# rp-schield.net
KiCad netlist of a schematic drawn in EAGLE
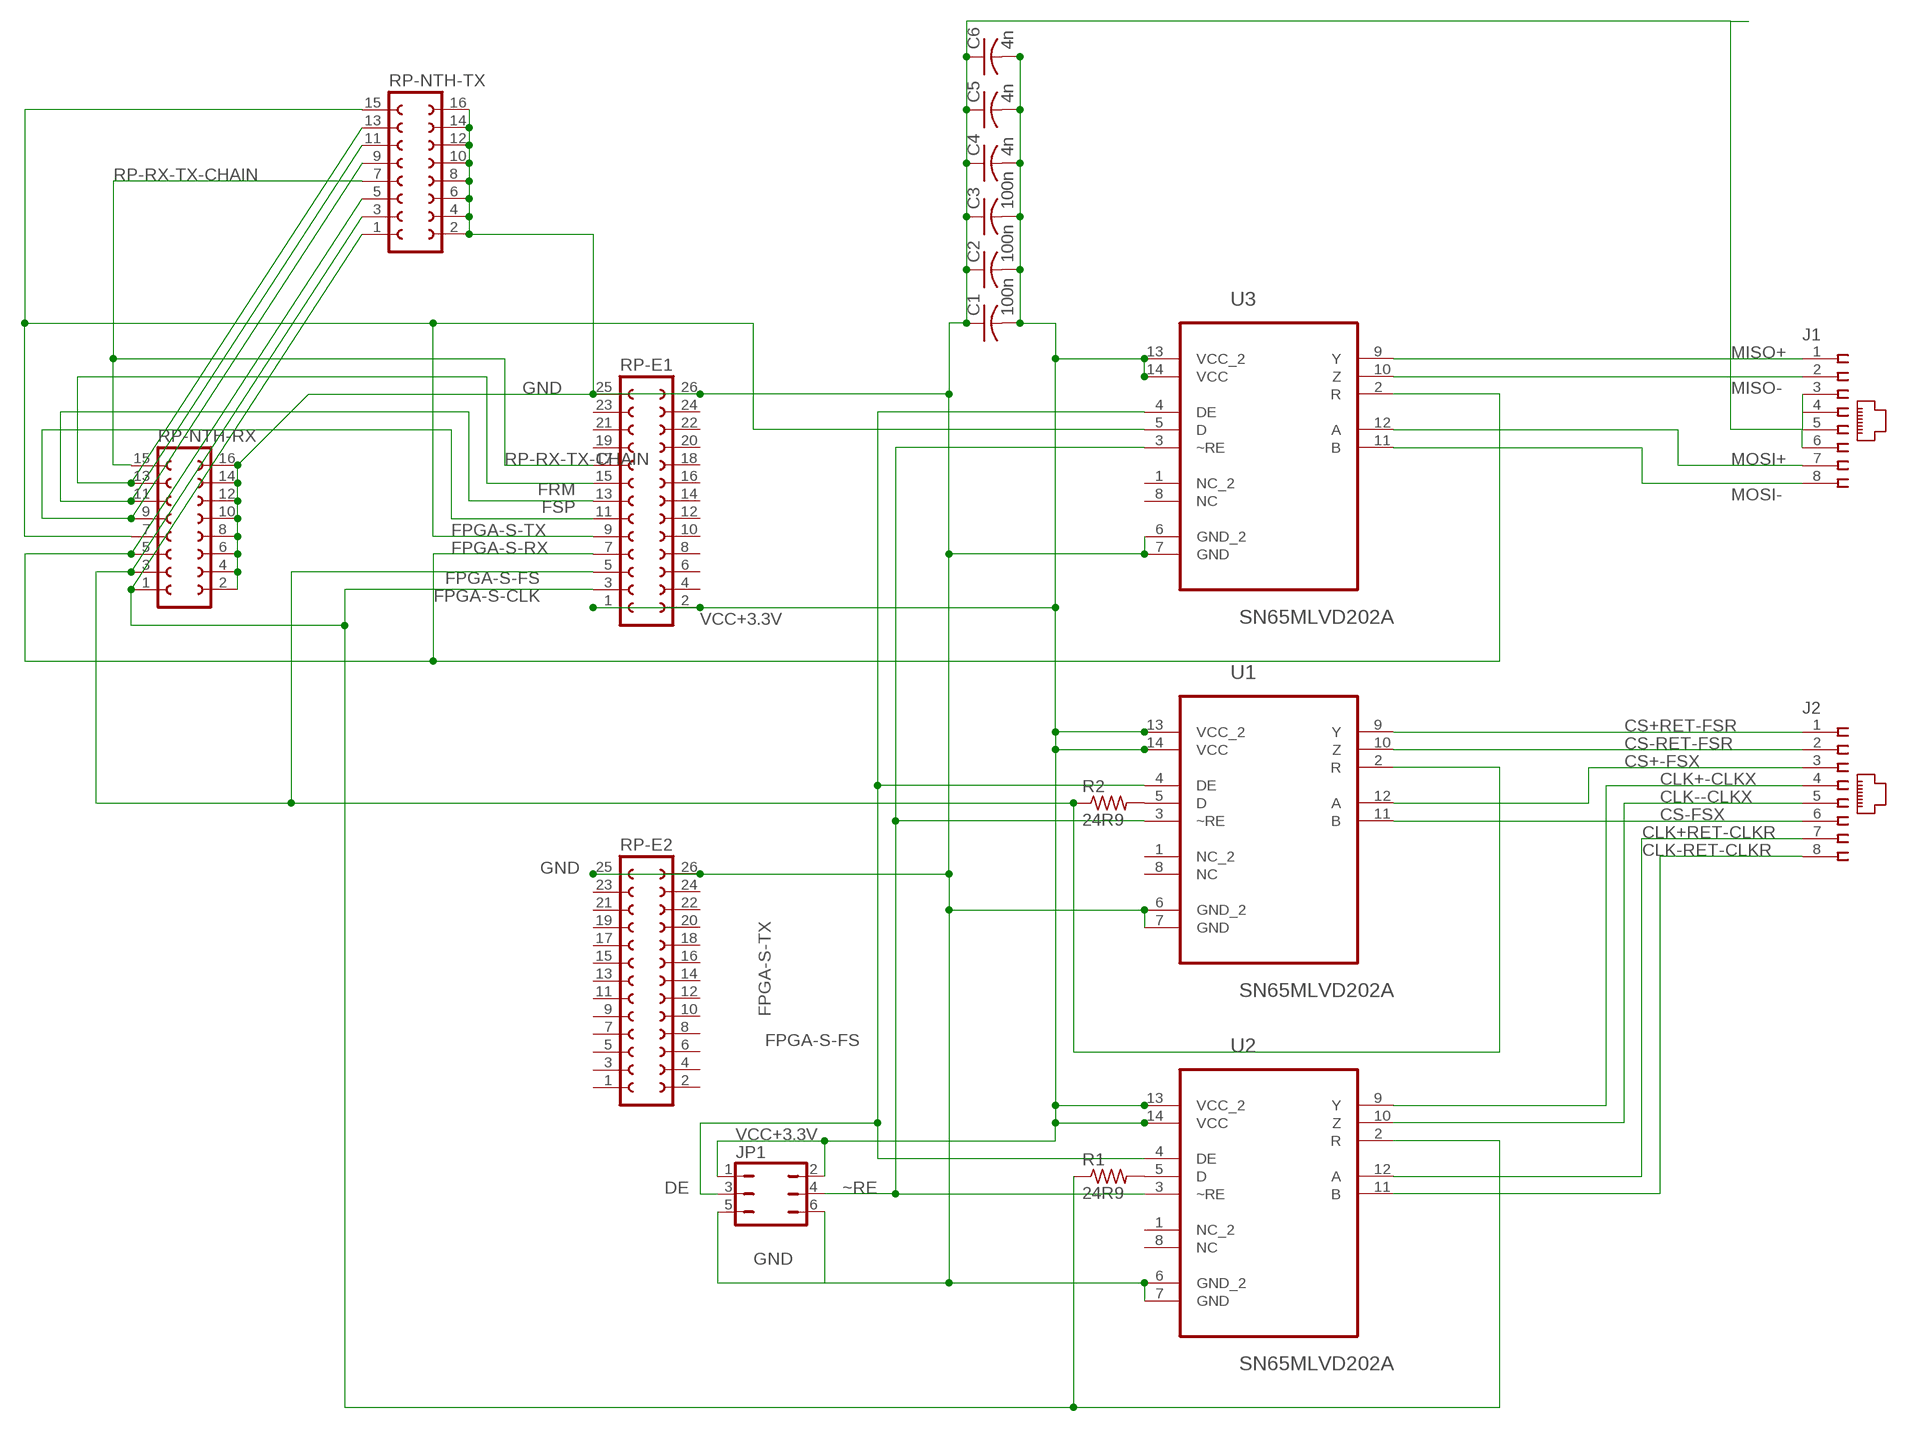
[diagram p0: schematic, sheet 1]

(export (version "E")
  (design (tool "Eeschema 10.0.6"))
  (components
    (comp (ref "C1")
      (value "100n")
      (footprint "eagle-import:C0805")
      (libsource (lib "eagle-import") (part "C-USC0805"))
    )
    (comp (ref "C2")
      (value "100n")
      (footprint "eagle-import:C0805")
      (libsource (lib "eagle-import") (part "C-USC0805"))
    )
    (comp (ref "C3")
      (value "100n")
      (footprint "eagle-import:C0805")
      (libsource (lib "eagle-import") (part "C-USC0805"))
    )
    (comp (ref "C4")
      (value "4n")
      (footprint "eagle-import:C0805")
      (libsource (lib "eagle-import") (part "C-USC0805"))
    )
    (comp (ref "C5")
      (value "4n")
      (footprint "eagle-import:C0805")
      (libsource (lib "eagle-import") (part "C-USC0805"))
    )
    (comp (ref "C6")
      (value "4n")
      (footprint "eagle-import:C0805")
      (libsource (lib "eagle-import") (part "C-USC0805"))
    )
    (comp (ref "J1")
      (value "557785-1-SHIELD")
      (footprint "eagle-import:557785-1")
      (libsource (lib "eagle-import") (part "557785-1-SHIELD"))
    )
    (comp (ref "J2")
      (value "557785-1-SHIELD")
      (footprint "eagle-import:557785-1")
      (libsource (lib "eagle-import") (part "557785-1-SHIELD"))
    )
    (comp (ref "JP1")
      (value "JP3Q")
      (footprint "eagle-import:JP3Q")
      (libsource (lib "eagle-import") (part "JP3Q"))
    )
    (comp (ref "R1")
      (value "24R9")
      (footprint "eagle-import:M1206")
      (libsource (lib "eagle-import") (part "R-US_M1206"))
    )
    (comp (ref "R2")
      (value "24R9")
      (footprint "eagle-import:M1206")
      (libsource (lib "eagle-import") (part "R-US_M1206"))
    )
    (comp (ref "RP-E1")
      (value "FE13-2")
      (footprint "eagle-import:FE13-2")
      (libsource (lib "eagle-import") (part "FE13-2"))
    )
    (comp (ref "RP-E2")
      (value "FE13-2")
      (footprint "eagle-import:FE13-2")
      (libsource (lib "eagle-import") (part "FE13-2"))
    )
    (comp (ref "RP-NTH-RX")
      (value "FE08-2")
      (footprint "eagle-import:FE08-2")
      (libsource (lib "eagle-import") (part "FE08-2"))
    )
    (comp (ref "RP-NTH-TX")
      (value "FE08-2")
      (footprint "eagle-import:FE08-2")
      (libsource (lib "eagle-import") (part "FE08-2"))
    )
    (comp (ref "U1")
      (value "SN65MLVD202A")
      (footprint "eagle-import:SOIC127P600X175-14N")
      (fields (field (name "MPN") "SN65MLVD205AD"))
      (libsource (lib "eagle-import") (part "SN65MLVD205AD"))
    )
    (comp (ref "U2")
      (value "SN65MLVD202A")
      (footprint "eagle-import:SOIC127P600X175-14N")
      (fields (field (name "MPN") "SN65MLVD205AD"))
      (libsource (lib "eagle-import") (part "SN65MLVD205AD"))
    )
    (comp (ref "U3")
      (value "SN65MLVD202A")
      (footprint "eagle-import:SOIC127P600X175-14N")
      (fields (field (name "MPN") "SN65MLVD205AD"))
      (libsource (lib "eagle-import") (part "SN65MLVD205AD"))
    )
  )
  (nets
    (net (code "1") (name "/CLK+-CLKX") (class "Default")
      (node (ref "J2") (pin "4") (pinfunction "4_4") (pintype "passive"))
      (node (ref "U2") (pin "9") (pinfunction "Y_9") (pintype "output"))
    )
    (net (code "2") (name "/CLK+RET-CLKR") (class "Default")
      (node (ref "J2") (pin "7") (pinfunction "7_7") (pintype "passive"))
      (node (ref "U2") (pin "12") (pinfunction "A_12") (pintype "output"))
    )
    (net (code "3") (name "/CLK--CLKX") (class "Default")
      (node (ref "J2") (pin "5") (pinfunction "5_5") (pintype "passive"))
      (node (ref "U2") (pin "10") (pinfunction "Z_10") (pintype "output"))
    )
    (net (code "4") (name "/CLK-RET-CLKR") (class "Default")
      (node (ref "J2") (pin "8") (pinfunction "8_8") (pintype "passive"))
      (node (ref "U2") (pin "11") (pinfunction "B_11") (pintype "output"))
    )
    (net (code "5") (name "/CS+-FSX") (class "Default")
      (node (ref "J2") (pin "3") (pinfunction "3_3") (pintype "passive"))
      (node (ref "U1") (pin "12") (pinfunction "A_12") (pintype "output"))
    )
    (net (code "6") (name "/CS+RET-FSR") (class "Default")
      (node (ref "J2") (pin "1") (pinfunction "1_1") (pintype "passive"))
      (node (ref "U1") (pin "9") (pinfunction "Y_9") (pintype "output"))
    )
    (net (code "7") (name "/CS-FSX") (class "Default")
      (node (ref "J2") (pin "6") (pinfunction "6_6") (pintype "passive"))
      (node (ref "U1") (pin "11") (pinfunction "B_11") (pintype "output"))
    )
    (net (code "8") (name "/CS-RET-FSR") (class "Default")
      (node (ref "J2") (pin "2") (pinfunction "2_2") (pintype "passive"))
      (node (ref "U1") (pin "10") (pinfunction "Z_10") (pintype "output"))
    )
    (net (code "9") (name "/DE") (class "Default")
      (node (ref "JP1") (pin "3") (pinfunction "3_3") (pintype "passive"))
      (node (ref "U1") (pin "4") (pinfunction "DE_4") (pintype "input"))
      (node (ref "U2") (pin "4") (pinfunction "DE_4") (pintype "input"))
      (node (ref "U3") (pin "4") (pinfunction "DE_4") (pintype "input"))
    )
    (net (code "10") (name "/FPGA-S-CLK") (class "Default")
      (node (ref "R1") (pin "1") (pinfunction "1_1") (pintype "passive"))
      (node (ref "RP-E1") (pin "3") (pinfunction "3_3") (pintype "passive"))
      (node (ref "RP-NTH-RX") (pin "1") (pinfunction "1_1") (pintype "passive"))
      (node (ref "RP-NTH-TX") (pin "1") (pinfunction "1_1") (pintype "passive"))
      (node (ref "U2") (pin "2") (pinfunction "R_2") (pintype "output"))
    )
    (net (code "11") (name "/FPGA-S-FS") (class "Default")
      (node (ref "R2") (pin "1") (pinfunction "1_1") (pintype "passive"))
      (node (ref "RP-E1") (pin "5") (pinfunction "5_5") (pintype "passive"))
      (node (ref "RP-NTH-RX") (pin "3") (pinfunction "3_3") (pintype "passive"))
      (node (ref "RP-NTH-TX") (pin "3") (pinfunction "3_3") (pintype "passive"))
      (node (ref "U1") (pin "2") (pinfunction "R_2") (pintype "output"))
    )
    (net (code "12") (name "/FPGA-S-RX") (class "Default")
      (node (ref "RP-E1") (pin "7") (pinfunction "7_7") (pintype "passive"))
      (node (ref "RP-NTH-RX") (pin "5") (pinfunction "5_5") (pintype "passive"))
      (node (ref "RP-NTH-TX") (pin "5") (pinfunction "5_5") (pintype "passive"))
      (node (ref "U3") (pin "2") (pinfunction "R_2") (pintype "output"))
    )
    (net (code "13") (name "/FPGA-S-TX") (class "Default")
      (node (ref "RP-E1") (pin "9") (pinfunction "9_9") (pintype "passive"))
      (node (ref "RP-NTH-RX") (pin "7") (pinfunction "7_7") (pintype "passive"))
      (node (ref "RP-NTH-TX") (pin "15") (pinfunction "15_15") (pintype "passive"))
      (node (ref "U3") (pin "5") (pinfunction "D_5") (pintype "input"))
    )
    (net (code "14") (name "/FRM") (class "Default")
      (node (ref "RP-E1") (pin "13") (pinfunction "13_13") (pintype "passive"))
      (node (ref "RP-NTH-RX") (pin "11") (pinfunction "11_11") (pintype "passive"))
      (node (ref "RP-NTH-TX") (pin "11") (pinfunction "11_11") (pintype "passive"))
    )
    (net (code "15") (name "/FSP") (class "Default")
      (node (ref "RP-E1") (pin "11") (pinfunction "11_11") (pintype "passive"))
      (node (ref "RP-NTH-RX") (pin "9") (pinfunction "9_9") (pintype "passive"))
      (node (ref "RP-NTH-TX") (pin "9") (pinfunction "9_9") (pintype "passive"))
    )
    (net (code "16") (name "/GND") (class "Default")
      (node (ref "C1") (pin "1") (pinfunction "1_1") (pintype "passive"))
      (node (ref "C2") (pin "1") (pinfunction "1_1") (pintype "passive"))
      (node (ref "C3") (pin "1") (pinfunction "1_1") (pintype "passive"))
      (node (ref "C4") (pin "1") (pinfunction "1_1") (pintype "passive"))
      (node (ref "C5") (pin "1") (pinfunction "1_1") (pintype "passive"))
      (node (ref "C6") (pin "1") (pinfunction "1_1") (pintype "passive"))
      (node (ref "J1") (pin "3") (pinfunction "3_3") (pintype "passive"))
      (node (ref "J1") (pin "4") (pinfunction "4_4") (pintype "passive"))
      (node (ref "J1") (pin "5") (pinfunction "5_5") (pintype "passive"))
      (node (ref "J1") (pin "6") (pinfunction "6_6") (pintype "passive"))
      (node (ref "JP1") (pin "5") (pinfunction "5_5") (pintype "passive"))
      (node (ref "JP1") (pin "6") (pinfunction "6_6") (pintype "passive"))
      (node (ref "RP-E1") (pin "25") (pinfunction "25_25") (pintype "passive"))
      (node (ref "RP-E1") (pin "26") (pinfunction "26_26") (pintype "passive"))
      (node (ref "RP-E2") (pin "25") (pinfunction "25_25") (pintype "passive"))
      (node (ref "RP-E2") (pin "26") (pinfunction "26_26") (pintype "passive"))
      (node (ref "RP-NTH-RX") (pin "10") (pinfunction "10_10") (pintype "passive"))
      (node (ref "RP-NTH-RX") (pin "12") (pinfunction "12_12") (pintype "passive"))
      (node (ref "RP-NTH-RX") (pin "14") (pinfunction "14_14") (pintype "passive"))
      (node (ref "RP-NTH-RX") (pin "16") (pinfunction "16_16") (pintype "passive"))
      (node (ref "RP-NTH-RX") (pin "2") (pinfunction "2_2") (pintype "passive"))
      (node (ref "RP-NTH-RX") (pin "4") (pinfunction "4_4") (pintype "passive"))
      (node (ref "RP-NTH-RX") (pin "6") (pinfunction "6_6") (pintype "passive"))
      (node (ref "RP-NTH-RX") (pin "8") (pinfunction "8_8") (pintype "passive"))
      (node (ref "RP-NTH-TX") (pin "10") (pinfunction "10_10") (pintype "passive"))
      (node (ref "RP-NTH-TX") (pin "12") (pinfunction "12_12") (pintype "passive"))
      (node (ref "RP-NTH-TX") (pin "14") (pinfunction "14_14") (pintype "passive"))
      (node (ref "RP-NTH-TX") (pin "16") (pinfunction "16_16") (pintype "passive"))
      (node (ref "RP-NTH-TX") (pin "2") (pinfunction "2_2") (pintype "passive"))
      (node (ref "RP-NTH-TX") (pin "4") (pinfunction "4_4") (pintype "passive"))
      (node (ref "RP-NTH-TX") (pin "6") (pinfunction "6_6") (pintype "passive"))
      (node (ref "RP-NTH-TX") (pin "8") (pinfunction "8_8") (pintype "passive"))
      (node (ref "U1") (pin "6") (pinfunction "GND_2_6") (pintype "passive"))
      (node (ref "U1") (pin "7") (pinfunction "GND_7") (pintype "passive"))
      (node (ref "U2") (pin "6") (pinfunction "GND_2_6") (pintype "passive"))
      (node (ref "U2") (pin "7") (pinfunction "GND_7") (pintype "passive"))
      (node (ref "U3") (pin "6") (pinfunction "GND_2_6") (pintype "passive"))
      (node (ref "U3") (pin "7") (pinfunction "GND_7") (pintype "passive"))
    )
    (net (code "17") (name "/MISO+") (class "Default")
      (node (ref "J1") (pin "1") (pinfunction "1_1") (pintype "passive"))
      (node (ref "U3") (pin "9") (pinfunction "Y_9") (pintype "output"))
    )
    (net (code "18") (name "/MISO-") (class "Default")
      (node (ref "J1") (pin "2") (pinfunction "2_2") (pintype "passive"))
      (node (ref "U3") (pin "10") (pinfunction "Z_10") (pintype "output"))
    )
    (net (code "19") (name "/MOSI+") (class "Default")
      (node (ref "J1") (pin "7") (pinfunction "7_7") (pintype "passive"))
      (node (ref "U3") (pin "12") (pinfunction "A_12") (pintype "output"))
    )
    (net (code "20") (name "/MOSI-") (class "Default")
      (node (ref "J1") (pin "8") (pinfunction "8_8") (pintype "passive"))
      (node (ref "U3") (pin "11") (pinfunction "B_11") (pintype "output"))
    )
    (net (code "21") (name "/RP-RX-TX-CHAIN") (class "Default")
      (node (ref "RP-E1") (pin "17") (pinfunction "17_17") (pintype "passive"))
      (node (ref "RP-NTH-RX") (pin "15") (pinfunction "15_15") (pintype "passive"))
      (node (ref "RP-NTH-TX") (pin "7") (pinfunction "7_7") (pintype "passive"))
    )
    (net (code "22") (name "/VCC+3.3V") (class "Default")
      (node (ref "C1") (pin "2") (pinfunction "2_2") (pintype "passive"))
      (node (ref "C2") (pin "2") (pinfunction "2_2") (pintype "passive"))
      (node (ref "C3") (pin "2") (pinfunction "2_2") (pintype "passive"))
      (node (ref "C4") (pin "2") (pinfunction "2_2") (pintype "passive"))
      (node (ref "C5") (pin "2") (pinfunction "2_2") (pintype "passive"))
      (node (ref "C6") (pin "2") (pinfunction "2_2") (pintype "passive"))
      (node (ref "JP1") (pin "1") (pinfunction "1_1") (pintype "passive"))
      (node (ref "JP1") (pin "2") (pinfunction "2_2") (pintype "passive"))
      (node (ref "RP-E1") (pin "1") (pinfunction "1_1") (pintype "passive"))
      (node (ref "RP-E1") (pin "2") (pinfunction "2_2") (pintype "passive"))
      (node (ref "U1") (pin "13") (pinfunction "VCC_2_13") (pintype "power_in"))
      (node (ref "U1") (pin "14") (pinfunction "VCC_14") (pintype "power_in"))
      (node (ref "U2") (pin "13") (pinfunction "VCC_2_13") (pintype "power_in"))
      (node (ref "U2") (pin "14") (pinfunction "VCC_14") (pintype "power_in"))
      (node (ref "U3") (pin "13") (pinfunction "VCC_2_13") (pintype "power_in"))
      (node (ref "U3") (pin "14") (pinfunction "VCC_14") (pintype "power_in"))
    )
    (net (code "23") (name "/~{RE}") (class "Default")
      (node (ref "JP1") (pin "4") (pinfunction "4_4") (pintype "passive"))
      (node (ref "U1") (pin "3") (pinfunction "~{RE}_3") (pintype "input"))
      (node (ref "U2") (pin "3") (pinfunction "~{RE}_3") (pintype "input"))
      (node (ref "U3") (pin "3") (pinfunction "~{RE}_3") (pintype "input"))
    )
    (net (code "24") (name "Net-(RP-E1-Pad15)") (class "Default")
      (node (ref "RP-E1") (pin "15") (pinfunction "15_15") (pintype "passive"))
      (node (ref "RP-NTH-RX") (pin "13") (pinfunction "13_13") (pintype "passive"))
      (node (ref "RP-NTH-TX") (pin "13") (pinfunction "13_13") (pintype "passive"))
    )
    (net (code "25") (name "Net-(U1-D)") (class "Default")
      (node (ref "R2") (pin "2") (pinfunction "2_2") (pintype "passive"))
      (node (ref "U1") (pin "5") (pinfunction "D_5") (pintype "input"))
    )
    (net (code "26") (name "Net-(U2-D)") (class "Default")
      (node (ref "R1") (pin "2") (pinfunction "2_2") (pintype "passive"))
      (node (ref "U2") (pin "5") (pinfunction "D_5") (pintype "input"))
    )
    (net (code "27") (name "unconnected-(RP-E1-Pad4)") (class "Default")
      (node (ref "RP-E1") (pin "4") (pinfunction "4_4") (pintype "passive"))
    )
    (net (code "28") (name "unconnected-(RP-E1-Pad6)") (class "Default")
      (node (ref "RP-E1") (pin "6") (pinfunction "6_6") (pintype "passive"))
    )
    (net (code "29") (name "unconnected-(RP-E1-Pad8)") (class "Default")
      (node (ref "RP-E1") (pin "8") (pinfunction "8_8") (pintype "passive"))
    )
    (net (code "30") (name "unconnected-(RP-E1-Pad10)") (class "Default")
      (node (ref "RP-E1") (pin "10") (pinfunction "10_10") (pintype "passive"))
    )
    (net (code "31") (name "unconnected-(RP-E1-Pad12)") (class "Default")
      (node (ref "RP-E1") (pin "12") (pinfunction "12_12") (pintype "passive"))
    )
    (net (code "32") (name "unconnected-(RP-E1-Pad14)") (class "Default")
      (node (ref "RP-E1") (pin "14") (pinfunction "14_14") (pintype "passive"))
    )
    (net (code "33") (name "unconnected-(RP-E1-Pad16)") (class "Default")
      (node (ref "RP-E1") (pin "16") (pinfunction "16_16") (pintype "passive"))
    )
    (net (code "34") (name "unconnected-(RP-E1-Pad18)") (class "Default")
      (node (ref "RP-E1") (pin "18") (pinfunction "18_18") (pintype "passive"))
    )
    (net (code "35") (name "unconnected-(RP-E1-Pad19)") (class "Default")
      (node (ref "RP-E1") (pin "19") (pinfunction "19_19") (pintype "passive"))
    )
    (net (code "36") (name "unconnected-(RP-E1-Pad20)") (class "Default")
      (node (ref "RP-E1") (pin "20") (pinfunction "20_20") (pintype "passive"))
    )
    (net (code "37") (name "unconnected-(RP-E1-Pad21)") (class "Default")
      (node (ref "RP-E1") (pin "21") (pinfunction "21_21") (pintype "passive"))
    )
    (net (code "38") (name "unconnected-(RP-E1-Pad22)") (class "Default")
      (node (ref "RP-E1") (pin "22") (pinfunction "22_22") (pintype "passive"))
    )
    (net (code "39") (name "unconnected-(RP-E1-Pad23)") (class "Default")
      (node (ref "RP-E1") (pin "23") (pinfunction "23_23") (pintype "passive"))
    )
    (net (code "40") (name "unconnected-(RP-E1-Pad24)") (class "Default")
      (node (ref "RP-E1") (pin "24") (pinfunction "24_24") (pintype "passive"))
    )
    (net (code "41") (name "unconnected-(RP-E2-Pad1)") (class "Default")
      (node (ref "RP-E2") (pin "1") (pinfunction "1_1") (pintype "passive"))
    )
    (net (code "42") (name "unconnected-(RP-E2-Pad2)") (class "Default")
      (node (ref "RP-E2") (pin "2") (pinfunction "2_2") (pintype "passive"))
    )
    (net (code "43") (name "unconnected-(RP-E2-Pad3)") (class "Default")
      (node (ref "RP-E2") (pin "3") (pinfunction "3_3") (pintype "passive"))
    )
    (net (code "44") (name "unconnected-(RP-E2-Pad4)") (class "Default")
      (node (ref "RP-E2") (pin "4") (pinfunction "4_4") (pintype "passive"))
    )
    (net (code "45") (name "unconnected-(RP-E2-Pad5)") (class "Default")
      (node (ref "RP-E2") (pin "5") (pinfunction "5_5") (pintype "passive"))
    )
    (net (code "46") (name "unconnected-(RP-E2-Pad6)") (class "Default")
      (node (ref "RP-E2") (pin "6") (pinfunction "6_6") (pintype "passive"))
    )
    (net (code "47") (name "unconnected-(RP-E2-Pad7)") (class "Default")
      (node (ref "RP-E2") (pin "7") (pinfunction "7_7") (pintype "passive"))
    )
    (net (code "48") (name "unconnected-(RP-E2-Pad8)") (class "Default")
      (node (ref "RP-E2") (pin "8") (pinfunction "8_8") (pintype "passive"))
    )
    (net (code "49") (name "unconnected-(RP-E2-Pad9)") (class "Default")
      (node (ref "RP-E2") (pin "9") (pinfunction "9_9") (pintype "passive"))
    )
    (net (code "50") (name "unconnected-(RP-E2-Pad10)") (class "Default")
      (node (ref "RP-E2") (pin "10") (pinfunction "10_10") (pintype "passive"))
    )
    (net (code "51") (name "unconnected-(RP-E2-Pad11)") (class "Default")
      (node (ref "RP-E2") (pin "11") (pinfunction "11_11") (pintype "passive"))
    )
    (net (code "52") (name "unconnected-(RP-E2-Pad12)") (class "Default")
      (node (ref "RP-E2") (pin "12") (pinfunction "12_12") (pintype "passive"))
    )
    (net (code "53") (name "unconnected-(RP-E2-Pad13)") (class "Default")
      (node (ref "RP-E2") (pin "13") (pinfunction "13_13") (pintype "passive"))
    )
    (net (code "54") (name "unconnected-(RP-E2-Pad14)") (class "Default")
      (node (ref "RP-E2") (pin "14") (pinfunction "14_14") (pintype "passive"))
    )
    (net (code "55") (name "unconnected-(RP-E2-Pad15)") (class "Default")
      (node (ref "RP-E2") (pin "15") (pinfunction "15_15") (pintype "passive"))
    )
    (net (code "56") (name "unconnected-(RP-E2-Pad16)") (class "Default")
      (node (ref "RP-E2") (pin "16") (pinfunction "16_16") (pintype "passive"))
    )
    (net (code "57") (name "unconnected-(RP-E2-Pad17)") (class "Default")
      (node (ref "RP-E2") (pin "17") (pinfunction "17_17") (pintype "passive"))
    )
    (net (code "58") (name "unconnected-(RP-E2-Pad18)") (class "Default")
      (node (ref "RP-E2") (pin "18") (pinfunction "18_18") (pintype "passive"))
    )
    (net (code "59") (name "unconnected-(RP-E2-Pad19)") (class "Default")
      (node (ref "RP-E2") (pin "19") (pinfunction "19_19") (pintype "passive"))
    )
    (net (code "60") (name "unconnected-(RP-E2-Pad20)") (class "Default")
      (node (ref "RP-E2") (pin "20") (pinfunction "20_20") (pintype "passive"))
    )
    (net (code "61") (name "unconnected-(RP-E2-Pad21)") (class "Default")
      (node (ref "RP-E2") (pin "21") (pinfunction "21_21") (pintype "passive"))
    )
    (net (code "62") (name "unconnected-(RP-E2-Pad22)") (class "Default")
      (node (ref "RP-E2") (pin "22") (pinfunction "22_22") (pintype "passive"))
    )
    (net (code "63") (name "unconnected-(RP-E2-Pad23)") (class "Default")
      (node (ref "RP-E2") (pin "23") (pinfunction "23_23") (pintype "passive"))
    )
    (net (code "64") (name "unconnected-(RP-E2-Pad24)") (class "Default")
      (node (ref "RP-E2") (pin "24") (pinfunction "24_24") (pintype "passive"))
    )
    (net (code "65") (name "unconnected-(U1-NC-Pad8)") (class "Default")
      (node (ref "U1") (pin "8") (pinfunction "NC_8") (pintype "no_connect"))
    )
    (net (code "66") (name "unconnected-(U1-NC_2-Pad1)") (class "Default")
      (node (ref "U1") (pin "1") (pinfunction "NC_2_1") (pintype "no_connect"))
    )
    (net (code "67") (name "unconnected-(U2-NC-Pad8)") (class "Default")
      (node (ref "U2") (pin "8") (pinfunction "NC_8") (pintype "no_connect"))
    )
    (net (code "68") (name "unconnected-(U2-NC_2-Pad1)") (class "Default")
      (node (ref "U2") (pin "1") (pinfunction "NC_2_1") (pintype "no_connect"))
    )
    (net (code "69") (name "unconnected-(U3-NC-Pad8)") (class "Default")
      (node (ref "U3") (pin "8") (pinfunction "NC_8") (pintype "no_connect"))
    )
    (net (code "70") (name "unconnected-(U3-NC_2-Pad1)") (class "Default")
      (node (ref "U3") (pin "1") (pinfunction "NC_2_1") (pintype "no_connect"))
    )
  )
)
